# SCH_Gantry-Sensor-PCB-SMD-6x-1_9_2024-09.net
KiCad netlist of a schematic drawn in EasyEDA
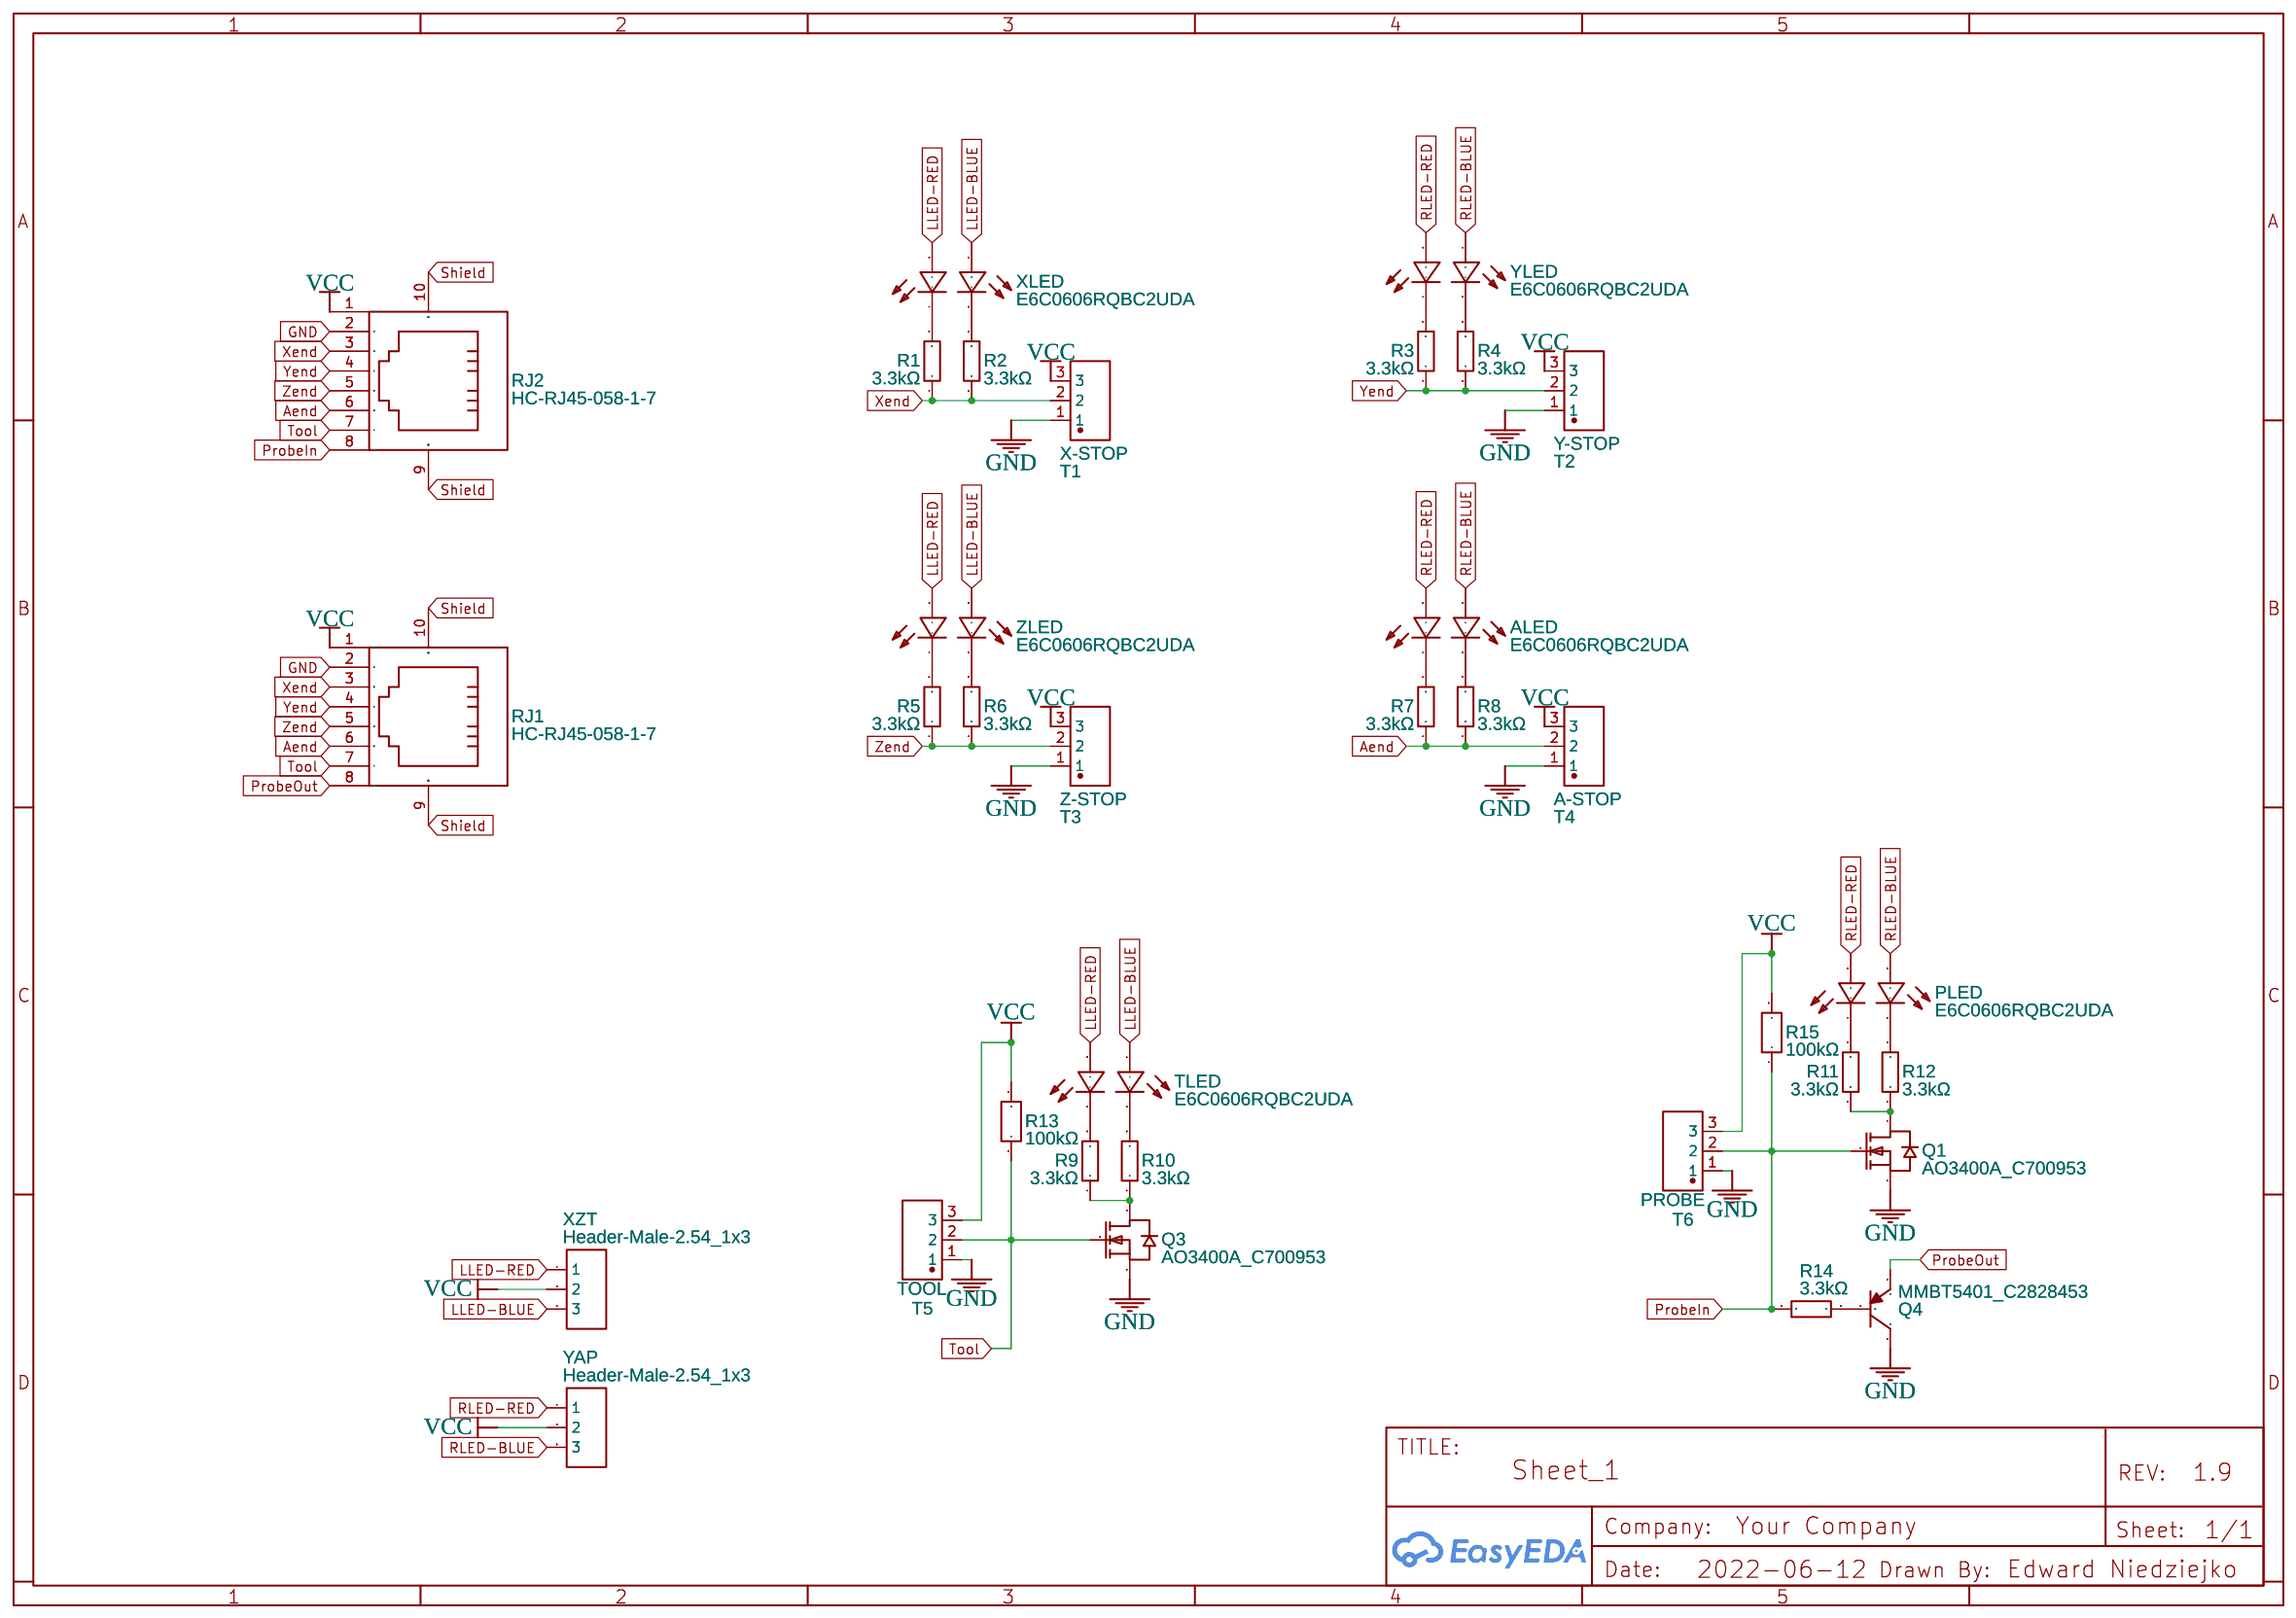
[diagram p0: schematic sheet]

(export (version "E")
  (design (tool "Eeschema 10.0.6"))
  (components
    (comp (ref "ALED")
      (value "E6C0606RQBC2UDA")
      (fields (field (name "Manufacturer") "ekinglux(亿晶源)"))
      (libsource (lib "") (part "E6C0606RQBC2UDA_1"))
    )
    (comp (ref "PLED")
      (value "E6C0606RQBC2UDA")
      (fields (field (name "Manufacturer") "ekinglux(亿晶源)"))
      (libsource (lib "") (part "E6C0606RQBC2UDA_4"))
    )
    (comp (ref "Q1")
      (value "AO3400A_C700953")
      (fields (field (name "Manufacturer Part") "AO3400A") (field (name "Manufacturer") "HUASHUO(华朔)"))
      (libsource (lib "") (part "AO3400A_C700953"))
    )
    (comp (ref "Q3")
      (value "AO3400A_C700953")
      (fields (field (name "Manufacturer Part") "AO3400A") (field (name "Manufacturer") "HUASHUO(华朔)"))
      (libsource (lib "") (part "AO3400A_C700953"))
    )
    (comp (ref "Q4")
      (value "MMBT5401_C2828453")
      (fields (field (name "Manufacturer Part") "MMBT5401 2L") (field (name "Manufacturer") "CBI(创基)"))
      (libsource (lib "") (part "MMBT5401_C2828453"))
    )
    (comp (ref "R1")
      (value "3.3kΩ")
      (fields (field (name "Manufacturer Part") "CR0402FF3301G") (field (name "Manufacturer") "LIZ(丽智电子)"))
      (libsource (lib "") (part "CR0402FF3301G"))
    )
    (comp (ref "R2")
      (value "3.3kΩ")
      (fields (field (name "Manufacturer Part") "CR0402FF3301G") (field (name "Manufacturer") "LIZ(丽智电子)"))
      (libsource (lib "") (part "CR0402FF3301G"))
    )
    (comp (ref "R3")
      (value "3.3kΩ")
      (fields (field (name "Manufacturer Part") "CR0402FF3301G") (field (name "Manufacturer") "LIZ(丽智电子)"))
      (libsource (lib "") (part "CR0402FF3301G"))
    )
    (comp (ref "R4")
      (value "3.3kΩ")
      (fields (field (name "Manufacturer Part") "CR0402FF3301G") (field (name "Manufacturer") "LIZ(丽智电子)"))
      (libsource (lib "") (part "CR0402FF3301G"))
    )
    (comp (ref "R5")
      (value "3.3kΩ")
      (fields (field (name "Manufacturer Part") "CR0402FF3301G") (field (name "Manufacturer") "LIZ(丽智电子)"))
      (libsource (lib "") (part "CR0402FF3301G"))
    )
    (comp (ref "R6")
      (value "3.3kΩ")
      (fields (field (name "Manufacturer Part") "CR0402FF3301G") (field (name "Manufacturer") "LIZ(丽智电子)"))
      (libsource (lib "") (part "CR0402FF3301G"))
    )
    (comp (ref "R7")
      (value "3.3kΩ")
      (fields (field (name "Manufacturer Part") "CR0402FF3301G") (field (name "Manufacturer") "LIZ(丽智电子)"))
      (libsource (lib "") (part "CR0402FF3301G"))
    )
    (comp (ref "R8")
      (value "3.3kΩ")
      (fields (field (name "Manufacturer Part") "CR0402FF3301G") (field (name "Manufacturer") "LIZ(丽智电子)"))
      (libsource (lib "") (part "CR0402FF3301G"))
    )
    (comp (ref "R9")
      (value "3.3kΩ")
      (fields (field (name "Manufacturer Part") "CR0402FF3301G") (field (name "Manufacturer") "LIZ(丽智电子)"))
      (libsource (lib "") (part "CR0402FF3301G"))
    )
    (comp (ref "R10")
      (value "3.3kΩ")
      (fields (field (name "Manufacturer Part") "CR0402FF3301G") (field (name "Manufacturer") "LIZ(丽智电子)"))
      (libsource (lib "") (part "CR0402FF3301G"))
    )
    (comp (ref "R11")
      (value "3.3kΩ")
      (fields (field (name "Manufacturer Part") "CR0402FF3301G") (field (name "Manufacturer") "LIZ(丽智电子)"))
      (libsource (lib "") (part "CR0402FF3301G"))
    )
    (comp (ref "R12")
      (value "3.3kΩ")
      (fields (field (name "Manufacturer Part") "CR0402FF3301G") (field (name "Manufacturer") "LIZ(丽智电子)"))
      (libsource (lib "") (part "CR0402FF3301G"))
    )
    (comp (ref "R13")
      (value "100kΩ")
      (fields (field (name "Manufacturer Part") "SCR0402F100K") (field (name "Manufacturer") "VO(翔胜)"))
      (libsource (lib "") (part "SCR0402F100K"))
    )
    (comp (ref "R14")
      (value "3.3kΩ")
      (fields (field (name "Manufacturer Part") "CR0402FF3301G") (field (name "Manufacturer") "LIZ(丽智电子)"))
      (libsource (lib "") (part "CR0402FF3301G_1"))
    )
    (comp (ref "R15")
      (value "100kΩ")
      (fields (field (name "Manufacturer Part") "SCR0402F100K") (field (name "Manufacturer") "VO(翔胜)"))
      (libsource (lib "") (part "SCR0402F100K"))
    )
    (comp (ref "RJ1")
      (value "HC-RJ45-058-1-7")
      (fields (field (name "Manufacturer") "HCTL(华灿天禄)"))
      (libsource (lib "") (part "HC-RJ45-058-1-7"))
    )
    (comp (ref "RJ2")
      (value "HC-RJ45-058-1-7")
      (fields (field (name "Manufacturer") "HCTL(华灿天禄)"))
      (libsource (lib "") (part "HC-RJ45-058-1-7"))
    )
    (comp (ref "T1")
      (value "X-STOP")
      (fields
        (field (name "Manufacturer Part") "KF2EDGV-3.5-3P")
        (field (name "Manufacturer") "Cixi Kefa Elec")
      )
      (libsource (lib "") (part "KF2EDGV-3.5-3P"))
    )
    (comp (ref "T2")
      (value "Y-STOP")
      (fields
        (field (name "Manufacturer Part") "KF2EDGV-3.5-3P")
        (field (name "Manufacturer") "Cixi Kefa Elec")
      )
      (libsource (lib "") (part "KF2EDGV-3.5-3P"))
    )
    (comp (ref "T3")
      (value "Z-STOP")
      (fields
        (field (name "Manufacturer Part") "KF2EDGV-3.5-3P")
        (field (name "Manufacturer") "Cixi Kefa Elec")
      )
      (libsource (lib "") (part "KF2EDGV-3.5-3P"))
    )
    (comp (ref "T4")
      (value "A-STOP")
      (fields
        (field (name "Manufacturer Part") "KF2EDGV-3.5-3P")
        (field (name "Manufacturer") "Cixi Kefa Elec")
      )
      (libsource (lib "") (part "KF2EDGV-3.5-3P"))
    )
    (comp (ref "T5")
      (value "TOOL")
      (fields
        (field (name "Manufacturer Part") "KF2EDGV-3.5-3P")
        (field (name "Manufacturer") "Cixi Kefa Elec")
      )
      (libsource (lib "") (part "KF2EDGV-3.5-3P_1"))
    )
    (comp (ref "T6")
      (value "PROBE")
      (fields
        (field (name "Manufacturer Part") "KF2EDGV-3.5-3P")
        (field (name "Manufacturer") "Cixi Kefa Elec")
      )
      (libsource (lib "") (part "KF2EDGV-3.5-3P_1"))
    )
    (comp (ref "TLED")
      (value "E6C0606RQBC2UDA")
      (fields (field (name "Manufacturer") "ekinglux(亿晶源)"))
      (libsource (lib "") (part "E6C0606RQBC2UDA_2"))
    )
    (comp (ref "XLED")
      (value "E6C0606RQBC2UDA")
      (fields (field (name "Manufacturer") "ekinglux(亿晶源)"))
      (libsource (lib "") (part "E6C0606RQBC2UDA"))
    )
    (comp (ref "XZT")
      (value "Header-Male-2.54_1x3")
      (fields (field (name "Manufacturer Part") "2.54-1*3P针") (field (name "Manufacturer") "BOOMELE(博穆精密)"))
      (libsource (lib "") (part "Header-Male-2.54_1x3_1"))
    )
    (comp (ref "YAP")
      (value "Header-Male-2.54_1x3")
      (fields (field (name "Manufacturer Part") "2.54-1*3P针") (field (name "Manufacturer") "BOOMELE(博穆精密)"))
      (libsource (lib "") (part "Header-Male-2.54_1x3"))
    )
    (comp (ref "YLED")
      (value "E6C0606RQBC2UDA")
      (fields (field (name "Manufacturer") "ekinglux(亿晶源)"))
      (libsource (lib "") (part "E6C0606RQBC2UDA_3"))
    )
    (comp (ref "ZLED")
      (value "E6C0606RQBC2UDA")
      (fields (field (name "Manufacturer") "ekinglux(亿晶源)"))
      (libsource (lib "") (part "E6C0606RQBC2UDA_5"))
    )
  )
  (nets
    (net (code "1") (name "Aend") (class "Default")
      (node (ref "R7") (pin "1") (pinfunction "1_1") (pintype "input"))
      (node (ref "R8") (pin "1") (pinfunction "1_1") (pintype "input"))
      (node (ref "RJ1") (pin "6") (pinfunction "6_6") (pintype "unspecified"))
      (node (ref "RJ2") (pin "6") (pinfunction "6_6") (pintype "unspecified"))
      (node (ref "T4") (pin "2") (pinfunction "2_2") (pintype "unspecified"))
    )
    (net (code "2") (name "GND") (class "Default")
      (node (ref "Q1") (pin "2") (pinfunction "S_2") (pintype "unspecified"))
      (node (ref "Q3") (pin "2") (pinfunction "S_2") (pintype "unspecified"))
      (node (ref "Q4") (pin "3") (pinfunction "C_3") (pintype "input"))
      (node (ref "RJ1") (pin "2") (pinfunction "2_2") (pintype "unspecified"))
      (node (ref "RJ2") (pin "2") (pinfunction "2_2") (pintype "unspecified"))
      (node (ref "T1") (pin "1") (pinfunction "1_1") (pintype "unspecified"))
      (node (ref "T2") (pin "1") (pinfunction "1_1") (pintype "unspecified"))
      (node (ref "T3") (pin "1") (pinfunction "1_1") (pintype "unspecified"))
      (node (ref "T4") (pin "1") (pinfunction "1_1") (pintype "unspecified"))
      (node (ref "T5") (pin "1") (pinfunction "1_1") (pintype "unspecified"))
      (node (ref "T6") (pin "1") (pinfunction "1_1") (pintype "unspecified"))
    )
    (net (code "3") (name "LLED-BLUE") (class "Default")
      (node (ref "TLED") (pin "1") (pinfunction "+_1") (pintype "unspecified"))
      (node (ref "XLED") (pin "1") (pinfunction "+_1") (pintype "unspecified"))
      (node (ref "XZT") (pin "3") (pinfunction "3_3") (pintype "input"))
      (node (ref "ZLED") (pin "1") (pinfunction "+_1") (pintype "unspecified"))
    )
    (net (code "4") (name "LLED-RED") (class "Default")
      (node (ref "TLED") (pin "3") (pinfunction "+_3") (pintype "unspecified"))
      (node (ref "XLED") (pin "3") (pinfunction "+_3") (pintype "unspecified"))
      (node (ref "XZT") (pin "1") (pinfunction "1_1") (pintype "input"))
      (node (ref "ZLED") (pin "3") (pinfunction "+_3") (pintype "unspecified"))
    )
    (net (code "5") (name "Net-(ALED---Pad2)") (class "Default")
      (node (ref "ALED") (pin "2") (pinfunction "-_2") (pintype "unspecified"))
      (node (ref "R8") (pin "2") (pinfunction "2_2") (pintype "input"))
    )
    (net (code "6") (name "Net-(ALED---Pad4)") (class "Default")
      (node (ref "ALED") (pin "4") (pinfunction "-_4") (pintype "unspecified"))
      (node (ref "R7") (pin "2") (pinfunction "2_2") (pintype "input"))
    )
    (net (code "7") (name "Net-(PLED---Pad2)") (class "Default")
      (node (ref "PLED") (pin "2") (pinfunction "-_2") (pintype "unspecified"))
      (node (ref "R12") (pin "2") (pinfunction "2_2") (pintype "input"))
    )
    (net (code "8") (name "Net-(PLED---Pad4)") (class "Default")
      (node (ref "PLED") (pin "4") (pinfunction "-_4") (pintype "unspecified"))
      (node (ref "R11") (pin "2") (pinfunction "2_2") (pintype "input"))
    )
    (net (code "9") (name "Net-(Q1-D)") (class "Default")
      (node (ref "Q1") (pin "3") (pinfunction "D_3") (pintype "unspecified"))
      (node (ref "R11") (pin "1") (pinfunction "1_1") (pintype "input"))
      (node (ref "R12") (pin "1") (pinfunction "1_1") (pintype "input"))
    )
    (net (code "10") (name "Net-(Q3-D)") (class "Default")
      (node (ref "Q3") (pin "3") (pinfunction "D_3") (pintype "unspecified"))
      (node (ref "R10") (pin "1") (pinfunction "1_1") (pintype "input"))
      (node (ref "R9") (pin "1") (pinfunction "1_1") (pintype "input"))
    )
    (net (code "11") (name "Net-(Q4-B)") (class "Default")
      (node (ref "Q4") (pin "2") (pinfunction "B_2") (pintype "input"))
      (node (ref "R14") (pin "1") (pinfunction "1_1") (pintype "input"))
    )
    (net (code "12") (name "Net-(R1-Pad2)") (class "Default")
      (node (ref "R1") (pin "2") (pinfunction "2_2") (pintype "input"))
      (node (ref "XLED") (pin "4") (pinfunction "-_4") (pintype "unspecified"))
    )
    (net (code "13") (name "Net-(R2-Pad2)") (class "Default")
      (node (ref "R2") (pin "2") (pinfunction "2_2") (pintype "input"))
      (node (ref "XLED") (pin "2") (pinfunction "-_2") (pintype "unspecified"))
    )
    (net (code "14") (name "Net-(R3-Pad2)") (class "Default")
      (node (ref "R3") (pin "2") (pinfunction "2_2") (pintype "input"))
      (node (ref "YLED") (pin "4") (pinfunction "-_4") (pintype "unspecified"))
    )
    (net (code "15") (name "Net-(R4-Pad2)") (class "Default")
      (node (ref "R4") (pin "2") (pinfunction "2_2") (pintype "input"))
      (node (ref "YLED") (pin "2") (pinfunction "-_2") (pintype "unspecified"))
    )
    (net (code "16") (name "Net-(R5-Pad2)") (class "Default")
      (node (ref "R5") (pin "2") (pinfunction "2_2") (pintype "input"))
      (node (ref "ZLED") (pin "4") (pinfunction "-_4") (pintype "unspecified"))
    )
    (net (code "17") (name "Net-(R6-Pad2)") (class "Default")
      (node (ref "R6") (pin "2") (pinfunction "2_2") (pintype "input"))
      (node (ref "ZLED") (pin "2") (pinfunction "-_2") (pintype "unspecified"))
    )
    (net (code "18") (name "Net-(R9-Pad2)") (class "Default")
      (node (ref "R9") (pin "2") (pinfunction "2_2") (pintype "input"))
      (node (ref "TLED") (pin "4") (pinfunction "-_4") (pintype "unspecified"))
    )
    (net (code "19") (name "Net-(R10-Pad2)") (class "Default")
      (node (ref "R10") (pin "2") (pinfunction "2_2") (pintype "input"))
      (node (ref "TLED") (pin "2") (pinfunction "-_2") (pintype "unspecified"))
    )
    (net (code "20") (name "ProbeIn") (class "Default")
      (node (ref "Q1") (pin "1") (pinfunction "G_1") (pintype "unspecified"))
      (node (ref "R14") (pin "2") (pinfunction "2_2") (pintype "input"))
      (node (ref "R15") (pin "1") (pinfunction "1_1") (pintype "unspecified"))
      (node (ref "RJ2") (pin "8") (pinfunction "8_8") (pintype "unspecified"))
      (node (ref "T6") (pin "2") (pinfunction "2_2") (pintype "unspecified"))
    )
    (net (code "21") (name "ProbeOut") (class "Default")
      (node (ref "Q4") (pin "1") (pinfunction "E_1") (pintype "input"))
      (node (ref "RJ1") (pin "8") (pinfunction "8_8") (pintype "unspecified"))
    )
    (net (code "22") (name "RLED-BLUE") (class "Default")
      (node (ref "ALED") (pin "1") (pinfunction "+_1") (pintype "unspecified"))
      (node (ref "PLED") (pin "1") (pinfunction "+_1") (pintype "unspecified"))
      (node (ref "YAP") (pin "3") (pinfunction "3_3") (pintype "input"))
      (node (ref "YLED") (pin "1") (pinfunction "+_1") (pintype "unspecified"))
    )
    (net (code "23") (name "RLED-RED") (class "Default")
      (node (ref "ALED") (pin "3") (pinfunction "+_3") (pintype "unspecified"))
      (node (ref "PLED") (pin "3") (pinfunction "+_3") (pintype "unspecified"))
      (node (ref "YAP") (pin "1") (pinfunction "1_1") (pintype "input"))
      (node (ref "YLED") (pin "3") (pinfunction "+_3") (pintype "unspecified"))
    )
    (net (code "24") (name "Shield") (class "Default")
      (node (ref "RJ1") (pin "10") (pinfunction "SHELL_10") (pintype "unspecified"))
      (node (ref "RJ1") (pin "9") (pinfunction "SHELL_9") (pintype "unspecified"))
      (node (ref "RJ2") (pin "10") (pinfunction "SHELL_10") (pintype "unspecified"))
      (node (ref "RJ2") (pin "9") (pinfunction "SHELL_9") (pintype "unspecified"))
    )
    (net (code "25") (name "Tool") (class "Default")
      (node (ref "Q3") (pin "1") (pinfunction "G_1") (pintype "unspecified"))
      (node (ref "R13") (pin "1") (pinfunction "1_1") (pintype "unspecified"))
      (node (ref "RJ1") (pin "7") (pinfunction "7_7") (pintype "unspecified"))
      (node (ref "RJ2") (pin "7") (pinfunction "7_7") (pintype "unspecified"))
      (node (ref "T5") (pin "2") (pinfunction "2_2") (pintype "unspecified"))
    )
    (net (code "26") (name "VCC") (class "Default")
      (node (ref "R13") (pin "2") (pinfunction "2_2") (pintype "unspecified"))
      (node (ref "R15") (pin "2") (pinfunction "2_2") (pintype "unspecified"))
      (node (ref "RJ1") (pin "1") (pinfunction "1_1") (pintype "unspecified"))
      (node (ref "RJ2") (pin "1") (pinfunction "1_1") (pintype "unspecified"))
      (node (ref "T1") (pin "3") (pinfunction "3_3") (pintype "unspecified"))
      (node (ref "T2") (pin "3") (pinfunction "3_3") (pintype "unspecified"))
      (node (ref "T3") (pin "3") (pinfunction "3_3") (pintype "unspecified"))
      (node (ref "T4") (pin "3") (pinfunction "3_3") (pintype "unspecified"))
      (node (ref "T5") (pin "3") (pinfunction "3_3") (pintype "unspecified"))
      (node (ref "T6") (pin "3") (pinfunction "3_3") (pintype "unspecified"))
      (node (ref "XZT") (pin "2") (pinfunction "2_2") (pintype "input"))
      (node (ref "YAP") (pin "2") (pinfunction "2_2") (pintype "input"))
    )
    (net (code "27") (name "Xend") (class "Default")
      (node (ref "R1") (pin "1") (pinfunction "1_1") (pintype "input"))
      (node (ref "R2") (pin "1") (pinfunction "1_1") (pintype "input"))
      (node (ref "RJ1") (pin "3") (pinfunction "3_3") (pintype "unspecified"))
      (node (ref "RJ2") (pin "3") (pinfunction "3_3") (pintype "unspecified"))
      (node (ref "T1") (pin "2") (pinfunction "2_2") (pintype "unspecified"))
    )
    (net (code "28") (name "Yend") (class "Default")
      (node (ref "R3") (pin "1") (pinfunction "1_1") (pintype "input"))
      (node (ref "R4") (pin "1") (pinfunction "1_1") (pintype "input"))
      (node (ref "RJ1") (pin "4") (pinfunction "4_4") (pintype "unspecified"))
      (node (ref "RJ2") (pin "4") (pinfunction "4_4") (pintype "unspecified"))
      (node (ref "T2") (pin "2") (pinfunction "2_2") (pintype "unspecified"))
    )
    (net (code "29") (name "Zend") (class "Default")
      (node (ref "R5") (pin "1") (pinfunction "1_1") (pintype "input"))
      (node (ref "R6") (pin "1") (pinfunction "1_1") (pintype "input"))
      (node (ref "RJ1") (pin "5") (pinfunction "5_5") (pintype "unspecified"))
      (node (ref "RJ2") (pin "5") (pinfunction "5_5") (pintype "unspecified"))
      (node (ref "T3") (pin "2") (pinfunction "2_2") (pintype "unspecified"))
    )
  )
)
